# do_an.net
KiCad netlist of a schematic drawn in Altium Designer
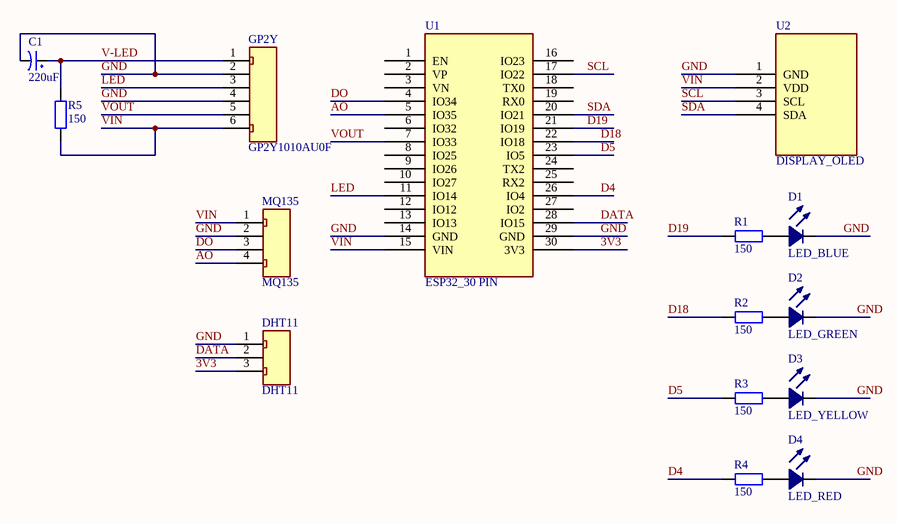
[diagram p0: do_an.SchDoc]

(export (version "E")
  (design (tool "Eeschema 10.0.6"))
  (components
    (comp (ref "C1")
      (value "220uF")
      (footprint "CP1.5/3.4")
      (description "Cap 1000uF/16V - 220uF/50V")
      (libsource (lib "syhaunguyen") (part "CP4"))
    )
    (comp (ref "D1")
      (value "LED_BLUE")
      (footprint "LED_5mm_BLUE")
      (description "LED PTH 5mm Blue.")
      (libsource (lib "LED") (part "LED_5mm_BLUE"))
    )
    (comp (ref "D2")
      (value "LED_GREEN")
      (footprint "LED_5mm_GREEN")
      (description "LED PTH 5mm Green.")
      (libsource (lib "LED") (part "LED_5mm_GREEN"))
    )
    (comp (ref "D3")
      (value "LED_YELLOW")
      (footprint "LED_5mm_YELLOW")
      (description "LED PTH 5mm Yellow.")
      (libsource (lib "LED") (part "LED_5mm_YELLOW"))
    )
    (comp (ref "D4")
      (value "LED_RED")
      (footprint "LED_5mm_RED")
      (description "LED PTH 5mm Red.")
      (libsource (lib "LED") (part "LED_5mm_RED"))
    )
    (comp (ref "DHT11")
      (value "DHT11")
      (footprint "JST-2.54-3P")
      (description "Female Connector JST 3 Vias, 2.54mm.")
      (libsource (lib "Connectors") (part "JST-2.54-3P"))
    )
    (comp (ref "GP2Y")
      (value "GP2Y1010AU0F")
      (footprint "JST-2.54-6P")
      (description "Female Connector JST 6 Vias, 2.54mm.")
      (libsource (lib "Connectors") (part "JST-2.54-6P"))
    )
    (comp (ref "MQ135")
      (value "MQ135")
      (footprint "JST-2.54-4P")
      (description "Female Connector JST 4 Vias, 2.54mm.")
      (libsource (lib "Connectors") (part "JST-2.54-4P"))
    )
    (comp (ref "R1")
      (value "150")
      (footprint "R1/4W")
      (description "Resistor 1/4W")
      (libsource (lib "syhaunguyen") (part "R1/4W"))
    )
    (comp (ref "R2")
      (value "150")
      (footprint "R1/4W")
      (description "Resistor 1/4W")
      (libsource (lib "syhaunguyen") (part "R1/4W"))
    )
    (comp (ref "R3")
      (value "150")
      (footprint "R1/4W")
      (description "Resistor 1/4W")
      (libsource (lib "syhaunguyen") (part "R1/4W"))
    )
    (comp (ref "R4")
      (value "150")
      (footprint "R1/4W")
      (description "Resistor 1/4W")
      (libsource (lib "syhaunguyen") (part "R1/4W"))
    )
    (comp (ref "R5")
      (value "150")
      (footprint "R1/4W")
      (description "Resistor 1/4W")
      (libsource (lib "syhaunguyen") (part "R1/4W"))
    )
    (comp (ref "U1")
      (value "ESP32_30 PIN")
      (footprint "ESP32_30")
      (description "Microcontoller Board 30 Pins Wifi 2.4GHz BLE 4.2 ESP32-WROOM-32D")
      (libsource (lib "Espressif Microcontrollers") (part "ESP32_30"))
    )
    (comp (ref "U2")
      (value "DISPLAY_OLED")
      (footprint "DISPLAY_OLED")
      (description "Display Oled 128x64 0.96\" I2C.")
      (libsource (lib "Displays") (part "DISPLAY_OLED"))
    )
  )
  (nets
    (net (code "1") (name "/3V3") (class "Default")
      (node (ref "DHT11") (pin "3") (pintype "passive"))
      (node (ref "U1") (pin "30") (pinfunction "3V3_30") (pintype "passive"))
    )
    (net (code "3") (name "/AO") (class "Default")
      (node (ref "MQ135") (pin "4") (pintype "passive"))
      (node (ref "U1") (pin "5") (pinfunction "IO35_5") (pintype "passive"))
    )
    (net (code "4") (name "/D4") (class "Default")
      (node (ref "R4") (pin "1") (pinfunction "1_1") (pintype "passive"))
      (node (ref "U1") (pin "26") (pinfunction "IO4_26") (pintype "passive"))
    )
    (net (code "5") (name "/D5") (class "Default")
      (node (ref "R3") (pin "1") (pinfunction "1_1") (pintype "passive"))
      (node (ref "U1") (pin "23") (pinfunction "IO5_23") (pintype "passive"))
    )
    (net (code "6") (name "/D18") (class "Default")
      (node (ref "R2") (pin "1") (pinfunction "1_1") (pintype "passive"))
      (node (ref "U1") (pin "22") (pinfunction "IO18_22") (pintype "passive"))
    )
    (net (code "7") (name "/D19") (class "Default")
      (node (ref "R1") (pin "1") (pinfunction "1_1") (pintype "passive"))
      (node (ref "U1") (pin "21") (pinfunction "IO19_21") (pintype "passive"))
    )
    (net (code "8") (name "/DATA") (class "Default")
      (node (ref "DHT11") (pin "2") (pintype "passive"))
      (node (ref "U1") (pin "28") (pinfunction "IO15_28") (pintype "passive"))
    )
    (net (code "9") (name "/DO") (class "Default")
      (node (ref "MQ135") (pin "3") (pintype "passive"))
      (node (ref "U1") (pin "4") (pinfunction "IO34_4") (pintype "passive"))
    )
    (net (code "10") (name "/GND") (class "Default")
      (node (ref "C1") (pin "2") (pinfunction "2_2") (pintype "passive"))
      (node (ref "D1") (pin "2") (pinfunction "2_2") (pintype "passive"))
      (node (ref "D2") (pin "2") (pinfunction "2_2") (pintype "passive"))
      (node (ref "D3") (pin "2") (pinfunction "2_2") (pintype "passive"))
      (node (ref "D4") (pin "2") (pinfunction "2_2") (pintype "passive"))
      (node (ref "DHT11") (pin "1") (pintype "passive"))
      (node (ref "GP2Y") (pin "2") (pintype "passive"))
      (node (ref "GP2Y") (pin "4") (pintype "passive"))
      (node (ref "MQ135") (pin "2") (pintype "passive"))
      (node (ref "U1") (pin "14") (pinfunction "GND_14") (pintype "passive"))
      (node (ref "U1") (pin "29") (pinfunction "GND_29") (pintype "passive"))
      (node (ref "U2") (pin "1") (pinfunction "GND_1") (pintype "tri_state"))
    )
    (net (code "11") (name "/LED") (class "Default")
      (node (ref "GP2Y") (pin "3") (pintype "passive"))
      (node (ref "U1") (pin "11") (pinfunction "IO14_11") (pintype "passive"))
    )
    (net (code "12") (name "/SCL") (class "Default")
      (node (ref "U1") (pin "17") (pinfunction "IO22_17") (pintype "passive"))
      (node (ref "U2") (pin "3") (pinfunction "SCL_3") (pintype "tri_state"))
    )
    (net (code "13") (name "/SDA") (class "Default")
      (node (ref "U1") (pin "20") (pinfunction "IO21_20") (pintype "passive"))
      (node (ref "U2") (pin "4") (pinfunction "SDA_4") (pintype "tri_state"))
    )
    (net (code "14") (name "/V-LED") (class "Default")
      (node (ref "C1") (pin "1") (pinfunction "1_1") (pintype "passive"))
      (node (ref "GP2Y") (pin "1") (pintype "passive"))
      (node (ref "R5") (pin "2") (pinfunction "2_2") (pintype "passive"))
    )
    (net (code "15") (name "/VIN") (class "Default")
      (node (ref "GP2Y") (pin "6") (pintype "passive"))
      (node (ref "MQ135") (pin "1") (pintype "passive"))
      (node (ref "R5") (pin "1") (pinfunction "1_1") (pintype "passive"))
      (node (ref "U1") (pin "15") (pinfunction "VIN_15") (pintype "passive"))
      (node (ref "U2") (pin "2") (pinfunction "VDD_2") (pintype "tri_state"))
    )
    (net (code "16") (name "/VOUT") (class "Default")
      (node (ref "GP2Y") (pin "5") (pintype "passive"))
      (node (ref "U1") (pin "7") (pinfunction "IO33_7") (pintype "passive"))
    )
    (net (code "17") (name "Net-(D1-Pad1)") (class "Default")
      (node (ref "D1") (pin "1") (pinfunction "1_1") (pintype "passive"))
      (node (ref "R1") (pin "2") (pinfunction "2_2") (pintype "passive"))
    )
    (net (code "18") (name "Net-(D2-Pad1)") (class "Default")
      (node (ref "D2") (pin "1") (pinfunction "1_1") (pintype "passive"))
      (node (ref "R2") (pin "2") (pinfunction "2_2") (pintype "passive"))
    )
    (net (code "19") (name "Net-(D3-Pad1)") (class "Default")
      (node (ref "D3") (pin "1") (pinfunction "1_1") (pintype "passive"))
      (node (ref "R3") (pin "2") (pinfunction "2_2") (pintype "passive"))
    )
    (net (code "20") (name "Net-(D4-Pad1)") (class "Default")
      (node (ref "D4") (pin "1") (pinfunction "1_1") (pintype "passive"))
      (node (ref "R4") (pin "2") (pinfunction "2_2") (pintype "passive"))
    )
    (net (code "21") (name "unconnected-(U1-EN-Pad1)") (class "Default")
      (node (ref "U1") (pin "1") (pinfunction "EN_1") (pintype "passive"))
    )
    (net (code "22") (name "unconnected-(U1-IO2-Pad27)") (class "Default")
      (node (ref "U1") (pin "27") (pinfunction "IO2_27") (pintype "passive"))
    )
    (net (code "23") (name "unconnected-(U1-IO12-Pad12)") (class "Default")
      (node (ref "U1") (pin "12") (pinfunction "IO12_12") (pintype "passive"))
    )
    (net (code "24") (name "unconnected-(U1-IO13-Pad13)") (class "Default")
      (node (ref "U1") (pin "13") (pinfunction "IO13_13") (pintype "passive"))
    )
    (net (code "25") (name "unconnected-(U1-IO23-Pad16)") (class "Default")
      (node (ref "U1") (pin "16") (pinfunction "IO23_16") (pintype "passive"))
    )
    (net (code "26") (name "unconnected-(U1-IO25-Pad8)") (class "Default")
      (node (ref "U1") (pin "8") (pinfunction "IO25_8") (pintype "passive"))
    )
    (net (code "27") (name "unconnected-(U1-IO26-Pad9)") (class "Default")
      (node (ref "U1") (pin "9") (pinfunction "IO26_9") (pintype "passive"))
    )
    (net (code "28") (name "unconnected-(U1-IO27-Pad10)") (class "Default")
      (node (ref "U1") (pin "10") (pinfunction "IO27_10") (pintype "passive"))
    )
    (net (code "29") (name "unconnected-(U1-IO32-Pad6)") (class "Default")
      (node (ref "U1") (pin "6") (pinfunction "IO32_6") (pintype "passive"))
    )
    (net (code "30") (name "unconnected-(U1-RX0-Pad19)") (class "Default")
      (node (ref "U1") (pin "19") (pinfunction "RX0_19") (pintype "passive"))
    )
    (net (code "31") (name "unconnected-(U1-RX2-Pad25)") (class "Default")
      (node (ref "U1") (pin "25") (pinfunction "RX2_25") (pintype "passive"))
    )
    (net (code "32") (name "unconnected-(U1-TX0-Pad18)") (class "Default")
      (node (ref "U1") (pin "18") (pinfunction "TX0_18") (pintype "passive"))
    )
    (net (code "33") (name "unconnected-(U1-TX2-Pad24)") (class "Default")
      (node (ref "U1") (pin "24") (pinfunction "TX2_24") (pintype "passive"))
    )
    (net (code "34") (name "unconnected-(U1-VN-Pad3)") (class "Default")
      (node (ref "U1") (pin "3") (pinfunction "VN_3") (pintype "passive"))
    )
    (net (code "35") (name "unconnected-(U1-VP-Pad2)") (class "Default")
      (node (ref "U1") (pin "2") (pinfunction "VP_2") (pintype "passive"))
    )
  )
)
